# 02_ESP12_Backup.net
KiCad netlist of a schematic drawn in Altium Designer
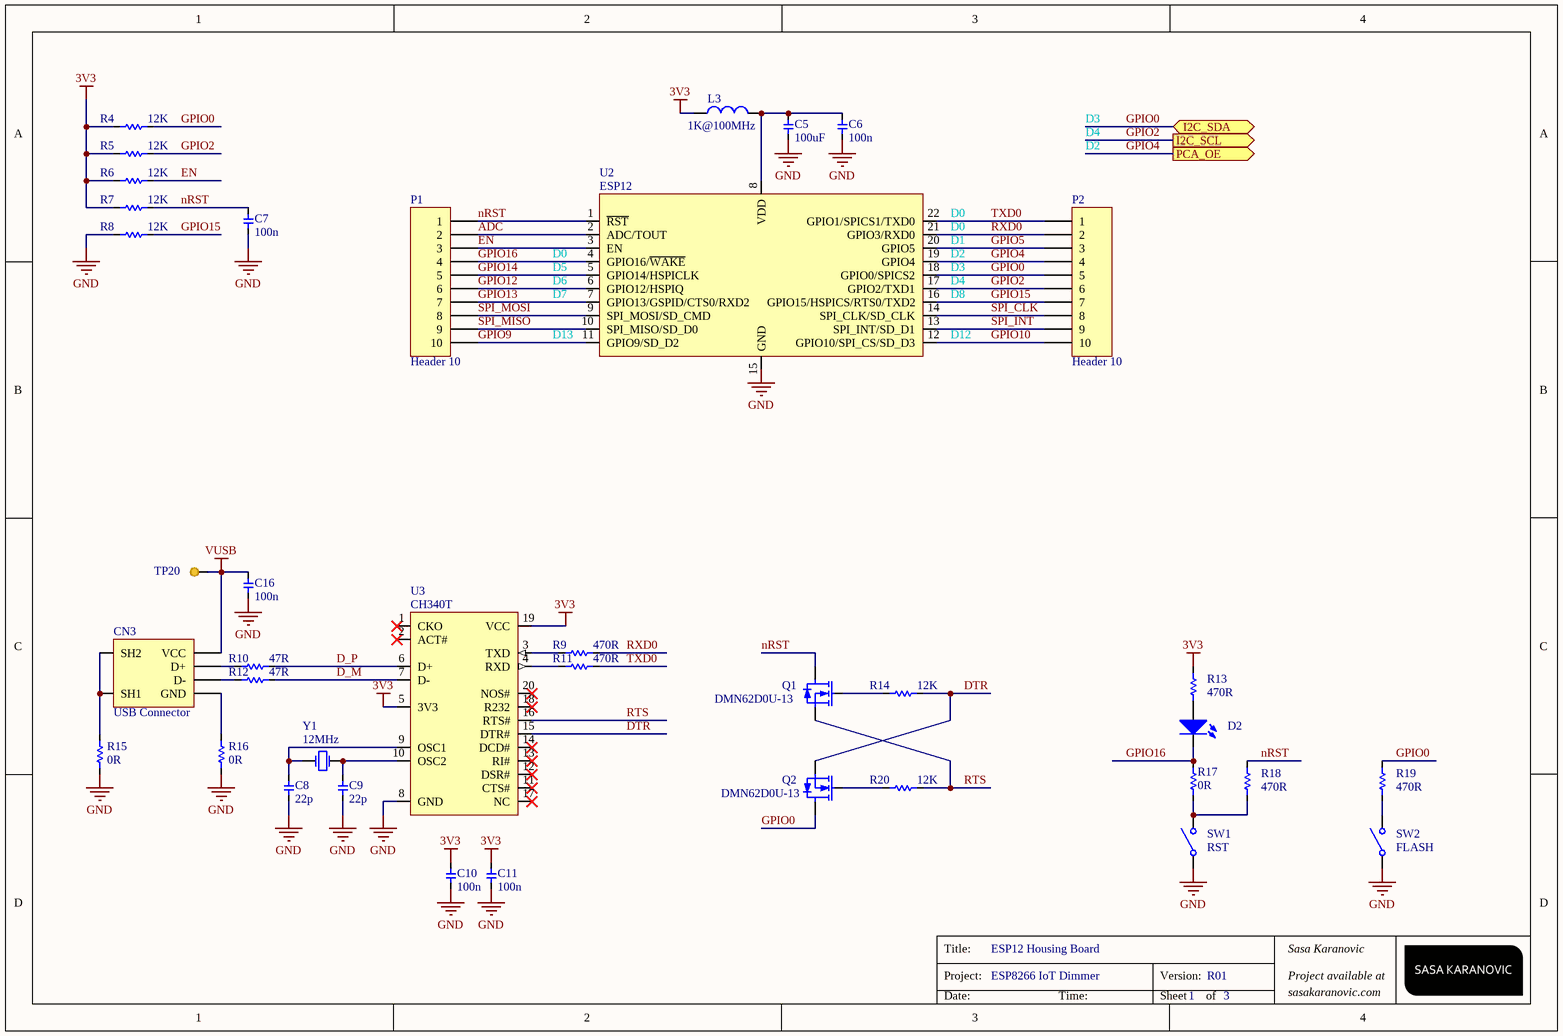
[diagram p0: 02_ESP12_Backup.SchDoc]

(export (version "E")
  (design (tool "Eeschema 10.0.6"))
  (components
    (comp (ref "C5")
      (value "100uF")
      (footprint "Moji Footprintovi:CAPC_1411_3528_X08N")
      (description "Capacitor")
      (fields
        (field (name "MANUFACTURER") "AVX Corporation")
        (field (name "MANUFACTURER PART NUMBER") "TAJB107M006RNJ")
      )
      (libsource (lib "Moji Schematici") (part "Cap"))
    )
    (comp (ref "C6")
      (value "100n")
      (footprint "Moji Footprintovi:0603 - CAP")
      (description "Capacitor")
      (fields (field (name "Comment") "Cap"))
      (libsource (lib "Moji Schematici") (part "Cap"))
    )
    (comp (ref "C7")
      (value "100n")
      (footprint "Moji Footprintovi:0603 - CAP")
      (description "Capacitor")
      (fields (field (name "Comment") "Cap"))
      (libsource (lib "Moji Schematici") (part "Cap"))
    )
    (comp (ref "C8")
      (value "22p")
      (footprint "Moji Footprintovi:0603 - CAP")
      (description "Capacitor")
      (fields (field (name "Comment") "Cap"))
      (libsource (lib "Moji Schematici") (part "Cap"))
    )
    (comp (ref "C9")
      (value "22p")
      (footprint "Moji Footprintovi:0603 - CAP")
      (description "Capacitor")
      (fields (field (name "Comment") "Cap"))
      (libsource (lib "Moji Schematici") (part "Cap"))
    )
    (comp (ref "C10")
      (value "100n")
      (footprint "Moji Footprintovi:0603 - CAP")
      (description "Capacitor")
      (fields (field (name "Comment") "Cap"))
      (libsource (lib "Moji Schematici") (part "Cap"))
    )
    (comp (ref "C11")
      (value "100n")
      (footprint "Moji Footprintovi:0603 - CAP")
      (description "Capacitor")
      (fields (field (name "Comment") "Cap"))
      (libsource (lib "Moji Schematici") (part "Cap"))
    )
    (comp (ref "C16")
      (value "100n")
      (footprint "Moji Footprintovi:0603 - CAP")
      (description "Capacitor")
      (fields (field (name "Comment") "Cap"))
      (libsource (lib "Moji Schematici") (part "Cap"))
    )
    (comp (ref "CN3")
      (value "USB Connector")
      (footprint "Moji Footprintovi:USB Mini SMD TOP")
      (description "Header, 4-Pin")
      (fields (field (name "PUBLISHER") "Altium Limited"))
      (libsource (lib "Moji Schematici") (part "USB Connector"))
    )
    (comp (ref "D2")
      (value "LED")
      (footprint "Moji Footprintovi:0603 Diode")
      (description "Typical RED GaAs LED")
      (fields (field (name "PUBLISHER") "Altium Limited"))
      (libsource (lib "Moji Schematici") (part "LED"))
    )
    (comp (ref "L3")
      (value "1K@100MHz")
      (footprint "0603")
      (description "FERRITE BEAD 1 KOHM 0603 1LN")
      (fields
        (field (name "MANUFACTURER") "TDK Corporation")
        (field (name "MANUFACTURER PART NUMBER") "MPZ1608S102ATA00")
      )
      (libsource (lib "Moji Schematici") (part "Inductor"))
    )
    (comp (ref "P1")
      (value "Header 10")
      (footprint "HDR1X10")
      (description "Header, 10-Pin")
      (fields (field (name "PUBLISHER") "Altium Limited"))
      (libsource (lib "") (part "Header 10_1"))
    )
    (comp (ref "P2")
      (value "Header 10")
      (footprint "HDR1X10")
      (description "Header, 10-Pin")
      (fields (field (name "PUBLISHER") "Altium Limited"))
      (libsource (lib "Moji Schematici") (part "Header 10"))
    )
    (comp (ref "Q1")
      (value "DMN62D0U-13")
      (footprint "Moji Footprintovi:SOT90P240X100-3N")
      (description "MOSFET N-CH 60V 0.38A")
      (fields
        (field (name "MANUFACTURER") "Diodes Incorporated")
        (field (name "DISTRIBUTOR PART NUMBER") "DMN62D0U-13DICT-ND")
      )
      (libsource (lib "Moji Schematici") (part "DMN62D0U-13"))
    )
    (comp (ref "Q2")
      (value "DMN62D0U-13")
      (footprint "Moji Footprintovi:SOT90P240X100-3N")
      (description "MOSFET N-CH 60V 0.38A")
      (fields
        (field (name "MANUFACTURER") "Diodes Incorporated")
        (field (name "DISTRIBUTOR PART NUMBER") "DMN62D0U-13DICT-ND")
      )
      (libsource (lib "Moji Schematici") (part "DMN62D0U-13"))
    )
    (comp (ref "R4")
      (value "12K")
      (footprint "Moji Footprintovi:0603")
      (description "Resistor")
      (fields (field (name "Comment") "Res"))
      (libsource (lib "Moji Schematici") (part "Res"))
    )
    (comp (ref "R5")
      (value "12K")
      (footprint "Moji Footprintovi:0603")
      (description "Resistor")
      (fields (field (name "Comment") "Res"))
      (libsource (lib "Moji Schematici") (part "Res"))
    )
    (comp (ref "R6")
      (value "12K")
      (footprint "Moji Footprintovi:0603")
      (description "Resistor")
      (fields (field (name "Comment") "Res"))
      (libsource (lib "Moji Schematici") (part "Res"))
    )
    (comp (ref "R7")
      (value "12K")
      (footprint "Moji Footprintovi:0603")
      (description "Resistor")
      (fields (field (name "Comment") "Res"))
      (libsource (lib "Moji Schematici") (part "Res"))
    )
    (comp (ref "R8")
      (value "12K")
      (footprint "Moji Footprintovi:0603")
      (description "Resistor")
      (fields (field (name "Comment") "Res"))
      (libsource (lib "Moji Schematici") (part "Res"))
    )
    (comp (ref "R9")
      (value "470R")
      (footprint "Moji Footprintovi:0603")
      (description "Resistor")
      (fields (field (name "Comment") "Res"))
      (libsource (lib "Moji Schematici") (part "Res"))
    )
    (comp (ref "R10")
      (value "47R")
      (footprint "Moji Footprintovi:0603")
      (description "Resistor")
      (fields (field (name "Comment") "Res"))
      (libsource (lib "Moji Schematici") (part "Res"))
    )
    (comp (ref "R11")
      (value "470R")
      (footprint "Moji Footprintovi:0603")
      (description "Resistor")
      (fields (field (name "Comment") "Res"))
      (libsource (lib "Moji Schematici") (part "Res"))
    )
    (comp (ref "R12")
      (value "47R")
      (footprint "Moji Footprintovi:0603")
      (description "Resistor")
      (fields (field (name "Comment") "Res"))
      (libsource (lib "Moji Schematici") (part "Res"))
    )
    (comp (ref "R13")
      (value "470R")
      (footprint "Moji Footprintovi:0603")
      (description "Resistor")
      (fields (field (name "Comment") "Res"))
      (libsource (lib "Moji Schematici") (part "Res"))
    )
    (comp (ref "R14")
      (value "12K")
      (footprint "Moji Footprintovi:0603")
      (description "Resistor")
      (fields (field (name "Comment") "Res"))
      (libsource (lib "Moji Schematici") (part "Res"))
    )
    (comp (ref "R15")
      (value "0R")
      (footprint "Moji Footprintovi:0603")
      (description "Resistor")
      (fields (field (name "Comment") "Res"))
      (libsource (lib "Moji Schematici") (part "Res"))
    )
    (comp (ref "R16")
      (value "0R")
      (footprint "Moji Footprintovi:0603")
      (description "Resistor")
      (fields (field (name "Comment") "Res"))
      (libsource (lib "Moji Schematici") (part "Res"))
    )
    (comp (ref "R17")
      (value "0R")
      (footprint "Moji Footprintovi:0603")
      (description "Resistor")
      (fields (field (name "Comment") "Res"))
      (libsource (lib "Moji Schematici") (part "Res"))
    )
    (comp (ref "R18")
      (value "470R")
      (footprint "Moji Footprintovi:0603")
      (description "Resistor")
      (fields (field (name "Comment") "Res"))
      (libsource (lib "Moji Schematici") (part "Res"))
    )
    (comp (ref "R19")
      (value "470R")
      (footprint "Moji Footprintovi:0603")
      (description "Resistor")
      (fields (field (name "Comment") "Res"))
      (libsource (lib "Moji Schematici") (part "Res"))
    )
    (comp (ref "R20")
      (value "12K")
      (footprint "Moji Footprintovi:0603")
      (description "Resistor")
      (fields (field (name "Comment") "Res"))
      (libsource (lib "Moji Schematici") (part "Res"))
    )
    (comp (ref "SW1")
      (value "Switch")
      (footprint "SMD Switch 2pin")
      (libsource (lib "Moji Schematici") (part "Switch"))
    )
    (comp (ref "SW2")
      (value "Switch")
      (footprint "SMD Switch 2pin")
      (libsource (lib "Moji Schematici") (part "Switch"))
    )
    (comp (ref "TP20")
      (value "Test Point 0.6mm")
      (footprint "Moji Footprintovi:TP_SMD_1mm")
      (libsource (lib "Moji Schematici") (part "TP"))
    )
    (comp (ref "U2")
      (value "ESP12")
      (footprint "Moji Footprintovi:ESP-12")
      (description "ESP8266 SMT Module - ESP-12S")
      (libsource (lib "Moji Schematici") (part "ESP12"))
    )
    (comp (ref "U3")
      (value "CH340T")
      (footprint "Moji Footprintovi:SOP20-5.30mm-0.65pitch")
      (description "CH340T USB-to-UART")
      (libsource (lib "Moji Schematici") (part "CH340T"))
    )
    (comp (ref "Y1")
      (value "12MHz")
      (footprint "Moji Footprintovi:XTAL SMD")
      (description "Crystal Oscillator")
      (fields (field (name "PUBLISHER") "Altium Limited"))
      (libsource (lib "Moji Schematici") (part "XTAL"))
    )
  )
  (nets
    (net (code "1") (name "/ADC") (class "Default")
      (node (ref "P1") (pin "2") (pinfunction "2_2") (pintype "passive"))
      (node (ref "U2") (pin "2") (pinfunction "ADC/TOUT_2") (pintype "passive"))
    )
    (net (code "2") (name "/DTR") (class "Default")
      (node (ref "Q2") (pin "3") (pinfunction "S_3") (pintype "passive"))
      (node (ref "R14") (pin "2") (pinfunction "2_2") (pintype "passive"))
      (node (ref "U3") (pin "15") (pinfunction "DTR#_15") (pintype "passive"))
    )
    (net (code "3") (name "/D_M") (class "Default")
      (node (ref "R12") (pin "1") (pinfunction "1_1") (pintype "passive"))
      (node (ref "U3") (pin "7") (pinfunction "D-_7") (pintype "passive"))
    )
    (net (code "4") (name "/D_P") (class "Default")
      (node (ref "R10") (pin "1") (pinfunction "1_1") (pintype "passive"))
      (node (ref "U3") (pin "6") (pinfunction "D+_6") (pintype "passive"))
    )
    (net (code "5") (name "/EN") (class "Default")
      (node (ref "P1") (pin "3") (pinfunction "3_3") (pintype "passive"))
      (node (ref "R6") (pin "2") (pinfunction "2_2") (pintype "passive"))
      (node (ref "U2") (pin "3") (pinfunction "EN_3") (pintype "passive"))
    )
    (net (code "6") (name "/GPIO0") (class "Default")
      (node (ref "P2") (pin "5") (pinfunction "5_5") (pintype "passive"))
      (node (ref "Q2") (pin "2") (pinfunction "D_2") (pintype "passive"))
      (node (ref "R19") (pin "2") (pinfunction "2_2") (pintype "passive"))
      (node (ref "R4") (pin "2") (pinfunction "2_2") (pintype "passive"))
      (node (ref "U2") (pin "18") (pinfunction "GPIO0/SPICS2_18") (pintype "passive"))
    )
    (net (code "7") (name "/GPIO2") (class "Default")
      (node (ref "P2") (pin "6") (pinfunction "6_6") (pintype "passive"))
      (node (ref "R5") (pin "2") (pinfunction "2_2") (pintype "passive"))
      (node (ref "U2") (pin "17") (pinfunction "GPIO2/TXD1_17") (pintype "passive"))
    )
    (net (code "8") (name "/GPIO4") (class "Default")
      (node (ref "P2") (pin "4") (pinfunction "4_4") (pintype "passive"))
      (node (ref "U2") (pin "19") (pinfunction "GPIO4_19") (pintype "passive"))
    )
    (net (code "9") (name "/GPIO5") (class "Default")
      (node (ref "P2") (pin "3") (pinfunction "3_3") (pintype "passive"))
      (node (ref "U2") (pin "20") (pinfunction "GPIO5_20") (pintype "passive"))
    )
    (net (code "10") (name "/GPIO9") (class "Default")
      (node (ref "P1") (pin "10") (pinfunction "10_10") (pintype "passive"))
      (node (ref "U2") (pin "11") (pinfunction "GPIO9/SD_D2_11") (pintype "passive"))
    )
    (net (code "11") (name "/GPIO10") (class "Default")
      (node (ref "P2") (pin "10") (pinfunction "10_10") (pintype "passive"))
      (node (ref "U2") (pin "12") (pinfunction "GPIO10/SPI_CS/SD_D3_12") (pintype "passive"))
    )
    (net (code "12") (name "/GPIO12") (class "Default")
      (node (ref "P1") (pin "6") (pinfunction "6_6") (pintype "passive"))
      (node (ref "U2") (pin "6") (pinfunction "GPIO12/HSPIQ_6") (pintype "passive"))
    )
    (net (code "13") (name "/GPIO13") (class "Default")
      (node (ref "P1") (pin "7") (pinfunction "7_7") (pintype "passive"))
      (node (ref "U2") (pin "7") (pinfunction "GPIO13/GSPID/CTS0/RXD2_7") (pintype "passive"))
    )
    (net (code "14") (name "/GPIO14") (class "Default")
      (node (ref "P1") (pin "5") (pinfunction "5_5") (pintype "passive"))
      (node (ref "U2") (pin "5") (pinfunction "GPIO14/HSPICLK_5") (pintype "passive"))
    )
    (net (code "15") (name "/GPIO15") (class "Default")
      (node (ref "P2") (pin "7") (pinfunction "7_7") (pintype "passive"))
      (node (ref "R8") (pin "2") (pinfunction "2_2") (pintype "passive"))
      (node (ref "U2") (pin "16") (pinfunction "GPIO15/HSPICS/RTS0/TXD2_16") (pintype "passive"))
    )
    (net (code "16") (name "/GPIO16") (class "Default")
      (node (ref "D2") (pin "K") (pinfunction "K_K") (pintype "passive"))
      (node (ref "P1") (pin "4") (pinfunction "4_4") (pintype "passive"))
      (node (ref "R17") (pin "1") (pinfunction "1_1") (pintype "passive"))
      (node (ref "U2") (pin "4") (pinfunction "GPIO16/~{WAKE}_4") (pintype "passive"))
    )
    (net (code "17") (name "/RTS") (class "Default")
      (node (ref "Q1") (pin "3") (pinfunction "S_3") (pintype "passive"))
      (node (ref "R20") (pin "2") (pinfunction "2_2") (pintype "passive"))
      (node (ref "U3") (pin "16") (pinfunction "RTS#_16") (pintype "passive"))
    )
    (net (code "18") (name "/RXD0") (class "Default")
      (node (ref "P2") (pin "2") (pinfunction "2_2") (pintype "passive"))
      (node (ref "R9") (pin "1") (pinfunction "1_1") (pintype "passive"))
      (node (ref "U2") (pin "21") (pinfunction "GPIO3/RXD0_21") (pintype "passive"))
    )
    (net (code "19") (name "/SPI_CLK") (class "Default")
      (node (ref "P2") (pin "8") (pinfunction "8_8") (pintype "passive"))
      (node (ref "U2") (pin "14") (pinfunction "SPI_CLK/SD_CLK_14") (pintype "passive"))
    )
    (net (code "20") (name "/SPI_INT") (class "Default")
      (node (ref "P2") (pin "9") (pinfunction "9_9") (pintype "passive"))
      (node (ref "U2") (pin "13") (pinfunction "SPI_INT/SD_D1_13") (pintype "passive"))
    )
    (net (code "21") (name "/SPI_MISO") (class "Default")
      (node (ref "P1") (pin "9") (pinfunction "9_9") (pintype "passive"))
      (node (ref "U2") (pin "10") (pinfunction "SPI_MISO/SD_D0_10") (pintype "passive"))
    )
    (net (code "22") (name "/SPI_MOSI") (class "Default")
      (node (ref "P1") (pin "8") (pinfunction "8_8") (pintype "passive"))
      (node (ref "U2") (pin "9") (pinfunction "SPI_MOSI/SD_CMD_9") (pintype "passive"))
    )
    (net (code "23") (name "/TXD0") (class "Default")
      (node (ref "P2") (pin "1") (pinfunction "1_1") (pintype "passive"))
      (node (ref "R11") (pin "1") (pinfunction "1_1") (pintype "passive"))
      (node (ref "U2") (pin "22") (pinfunction "GPIO1/SPICS1/TXD0_22") (pintype "passive"))
    )
    (net (code "24") (name "/nRST") (class "Default")
      (node (ref "C7") (pin "2") (pinfunction "2_2") (pintype "passive"))
      (node (ref "P1") (pin "1") (pinfunction "1_1") (pintype "passive"))
      (node (ref "Q1") (pin "2") (pinfunction "D_2") (pintype "passive"))
      (node (ref "R18") (pin "2") (pinfunction "2_2") (pintype "passive"))
      (node (ref "R7") (pin "2") (pinfunction "2_2") (pintype "passive"))
      (node (ref "U2") (pin "1") (pinfunction "~{RST}_1") (pintype "passive"))
    )
    (net (code "25") (name "3V3") (class "Default")
      (node (ref "C10") (pin "2") (pinfunction "2_2") (pintype "passive"))
      (node (ref "C11") (pin "2") (pinfunction "2_2") (pintype "passive"))
      (node (ref "L3") (pin "1") (pinfunction "1_1") (pintype "passive"))
      (node (ref "R13") (pin "2") (pinfunction "2_2") (pintype "passive"))
      (node (ref "R4") (pin "1") (pinfunction "1_1") (pintype "passive"))
      (node (ref "R5") (pin "1") (pinfunction "1_1") (pintype "passive"))
      (node (ref "R6") (pin "1") (pinfunction "1_1") (pintype "passive"))
      (node (ref "R7") (pin "1") (pinfunction "1_1") (pintype "passive"))
      (node (ref "U3") (pin "19") (pinfunction "VCC_19") (pintype "power_in"))
      (node (ref "U3") (pin "5") (pinfunction "3V3_5") (pintype "power_in"))
    )
    (net (code "26") (name "GND") (class "Default")
      (node (ref "C10") (pin "1") (pinfunction "1_1") (pintype "passive"))
      (node (ref "C11") (pin "1") (pinfunction "1_1") (pintype "passive"))
      (node (ref "C16") (pin "1") (pinfunction "1_1") (pintype "passive"))
      (node (ref "C5") (pin "1") (pinfunction "1_1") (pintype "passive"))
      (node (ref "C6") (pin "1") (pinfunction "1_1") (pintype "passive"))
      (node (ref "C7") (pin "1") (pinfunction "1_1") (pintype "passive"))
      (node (ref "C8") (pin "1") (pinfunction "1_1") (pintype "passive"))
      (node (ref "C9") (pin "1") (pinfunction "1_1") (pintype "passive"))
      (node (ref "R15") (pin "2") (pinfunction "2_2") (pintype "passive"))
      (node (ref "R16") (pin "2") (pinfunction "2_2") (pintype "passive"))
      (node (ref "R8") (pin "1") (pinfunction "1_1") (pintype "passive"))
      (node (ref "SW1") (pin "1") (pinfunction "COMMON1_1") (pintype "passive"))
      (node (ref "SW2") (pin "1") (pinfunction "COMMON1_1") (pintype "passive"))
      (node (ref "U2") (pin "15") (pinfunction "GND_15") (pintype "passive"))
      (node (ref "U3") (pin "8") (pinfunction "GND_8") (pintype "power_in"))
    )
    (net (code "27") (name "Net-(CN3-PadD+)") (class "Default")
      (node (ref "CN3") (pin "D+") (pinfunction "D+_D+") (pintype "passive"))
      (node (ref "R10") (pin "2") (pinfunction "2_2") (pintype "passive"))
    )
    (net (code "28") (name "Net-(CN3-PadD-)") (class "Default")
      (node (ref "CN3") (pin "D-") (pinfunction "D-_D-") (pintype "passive"))
      (node (ref "R12") (pin "2") (pinfunction "2_2") (pintype "passive"))
    )
    (net (code "29") (name "Net-(CN3-PadGND)") (class "Default")
      (node (ref "CN3") (pin "GND") (pinfunction "GND_GND") (pintype "passive"))
      (node (ref "R16") (pin "1") (pinfunction "1_1") (pintype "passive"))
    )
    (net (code "30") (name "Net-(CN3-PadSH1)") (class "Default")
      (node (ref "CN3") (pin "SH1") (pinfunction "SH1_SH1") (pintype "passive"))
      (node (ref "CN3") (pin "SH2") (pinfunction "SH2_SH2") (pintype "passive"))
      (node (ref "R15") (pin "1") (pinfunction "1_1") (pintype "passive"))
    )
    (net (code "31") (name "Net-(D2-PadA)") (class "Default")
      (node (ref "D2") (pin "A") (pinfunction "A_A") (pintype "passive"))
      (node (ref "R13") (pin "1") (pinfunction "1_1") (pintype "passive"))
    )
    (net (code "32") (name "Net-(Q1-G)") (class "Default")
      (node (ref "Q1") (pin "1") (pinfunction "G_1") (pintype "passive"))
      (node (ref "R14") (pin "1") (pinfunction "1_1") (pintype "passive"))
    )
    (net (code "33") (name "Net-(Q2-G)") (class "Default")
      (node (ref "Q2") (pin "1") (pinfunction "G_1") (pintype "passive"))
      (node (ref "R20") (pin "1") (pinfunction "1_1") (pintype "passive"))
    )
    (net (code "34") (name "Net-(SW1-COMMON2)") (class "Default")
      (node (ref "R17") (pin "2") (pinfunction "2_2") (pintype "passive"))
      (node (ref "R18") (pin "1") (pinfunction "1_1") (pintype "passive"))
      (node (ref "SW1") (pin "2") (pinfunction "COMMON2_2") (pintype "passive"))
    )
    (net (code "35") (name "Net-(SW2-COMMON2)") (class "Default")
      (node (ref "R19") (pin "1") (pinfunction "1_1") (pintype "passive"))
      (node (ref "SW2") (pin "2") (pinfunction "COMMON2_2") (pintype "passive"))
    )
    (net (code "36") (name "Net-(U2-VDD)") (class "Default")
      (node (ref "C5") (pin "2") (pinfunction "2_2") (pintype "passive"))
      (node (ref "C6") (pin "2") (pinfunction "2_2") (pintype "passive"))
      (node (ref "L3") (pin "2") (pinfunction "2_2") (pintype "passive"))
      (node (ref "U2") (pin "8") (pinfunction "VDD_8") (pintype "passive"))
    )
    (net (code "37") (name "Net-(U3-OSC1)") (class "Default")
      (node (ref "C8") (pin "2") (pinfunction "2_2") (pintype "passive"))
      (node (ref "U3") (pin "9") (pinfunction "OSC1_9") (pintype "passive"))
      (node (ref "Y1") (pin "1") (pinfunction "OSC1_1") (pintype "passive"))
    )
    (net (code "38") (name "Net-(U3-OSC2)") (class "Default")
      (node (ref "C9") (pin "2") (pinfunction "2_2") (pintype "passive"))
      (node (ref "U3") (pin "10") (pinfunction "OSC2_10") (pintype "passive"))
      (node (ref "Y1") (pin "2") (pinfunction "OSC2_2") (pintype "passive"))
    )
    (net (code "39") (name "Net-(U3-RXD)") (class "Default")
      (node (ref "R11") (pin "2") (pinfunction "2_2") (pintype "passive"))
      (node (ref "U3") (pin "4") (pinfunction "RXD_4") (pintype "output"))
    )
    (net (code "40") (name "Net-(U3-TXD)") (class "Default")
      (node (ref "R9") (pin "2") (pinfunction "2_2") (pintype "passive"))
      (node (ref "U3") (pin "3") (pinfunction "TXD_3") (pintype "input"))
    )
    (net (code "41") (name "VUSB") (class "Default")
      (node (ref "C16") (pin "2") (pinfunction "2_2") (pintype "passive"))
      (node (ref "CN3") (pin "VCC") (pinfunction "VCC_VCC") (pintype "passive"))
      (node (ref "TP20") (pin "1") (pinfunction "1_1") (pintype "passive"))
    )
    (net (code "42") (name "unconnected-(U3-ACT#-Pad2)") (class "Default")
      (node (ref "U3") (pin "2") (pinfunction "ACT#_2") (pintype "passive+no_connect"))
    )
    (net (code "43") (name "unconnected-(U3-CKO-Pad1)") (class "Default")
      (node (ref "U3") (pin "1") (pinfunction "CKO_1") (pintype "passive+no_connect"))
    )
    (net (code "44") (name "unconnected-(U3-CTS#-Pad11)") (class "Default")
      (node (ref "U3") (pin "11") (pinfunction "CTS#_11") (pintype "passive+no_connect"))
    )
    (net (code "45") (name "unconnected-(U3-DCD#-Pad14)") (class "Default")
      (node (ref "U3") (pin "14") (pinfunction "DCD#_14") (pintype "passive+no_connect"))
    )
    (net (code "46") (name "unconnected-(U3-DSR#-Pad12)") (class "Default")
      (node (ref "U3") (pin "12") (pinfunction "DSR#_12") (pintype "passive+no_connect"))
    )
    (net (code "47") (name "unconnected-(U3-NC-Pad17)") (class "Default")
      (node (ref "U3") (pin "17") (pinfunction "NC_17") (pintype "passive+no_connect"))
    )
    (net (code "48") (name "unconnected-(U3-NOS#-Pad20)") (class "Default")
      (node (ref "U3") (pin "20") (pinfunction "NOS#_20") (pintype "passive+no_connect"))
    )
    (net (code "49") (name "unconnected-(U3-R232-Pad18)") (class "Default")
      (node (ref "U3") (pin "18") (pinfunction "R232_18") (pintype "passive+no_connect"))
    )
    (net (code "50") (name "unconnected-(U3-RI#-Pad13)") (class "Default")
      (node (ref "U3") (pin "13") (pinfunction "RI#_13") (pintype "passive+no_connect"))
    )
  )
)
